# Codeshelf-0011_v01.net
KiCad netlist of a schematic drawn in EAGLE
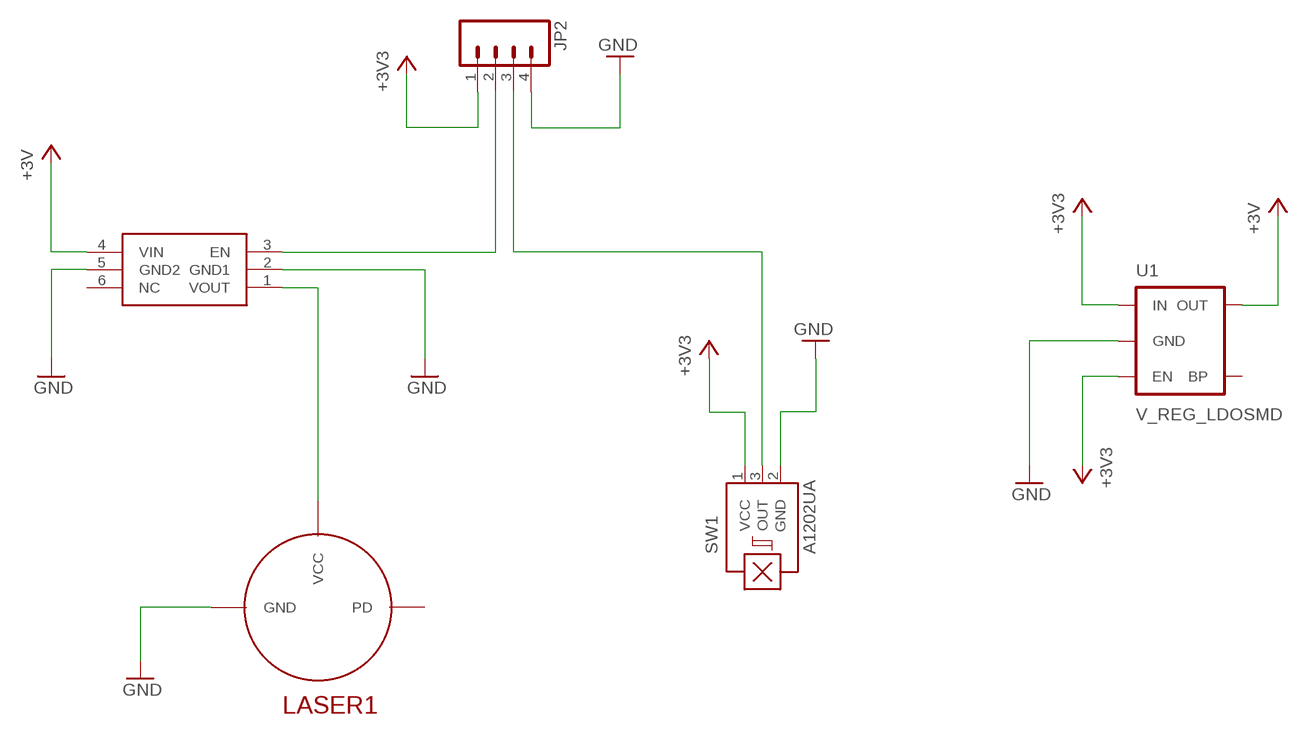
[diagram p0: schematic, sheet 1]

(export (version "E")
  (design (tool "Eeschema 10.0.6"))
  (components
    (comp (ref "JP2")
      (value "M04PTH")
      (footprint "eagle-import:1X04")
      (libsource (lib "eagle-import") (part "M04PTH"))
    )
    (comp (ref "LASER1")
      (value "LMAPCD-650-06")
      (footprint "eagle-import:LMAPCD-650-06")
      (libsource (lib "eagle-import") (part "LMAPCD-650-06"))
    )
    (comp (ref "SW1")
      (value "A1202UA")
      (footprint "eagle-import:SIP3-UA")
      (libsource (lib "eagle-import") (part "A12?UA02"))
    )
    (comp (ref "U1")
      (value "V_REG_LDOSMD")
      (footprint "eagle-import:SOT23-5")
      (libsource (lib "eagle-import") (part "V_REG_LDOSMD"))
    )
    (comp (ref "U2")
      (value "MIC94061C6")
      (footprint "eagle-import:SC70-6L")
      (libsource (lib "eagle-import") (part "MIC94061C6"))
    )
  )
  (nets
    (net (code "1") (name "+3V") (class "Default")
      (node (ref "U1") (pin "5") (pinfunction "OUT_5") (pintype "passive"))
      (node (ref "U2") (pin "4") (pinfunction "VIN_4") (pintype "bidirectional"))
    )
    (net (code "2") (name "+3V3") (class "Default")
      (node (ref "JP2") (pin "1") (pinfunction "1_1") (pintype "passive"))
      (node (ref "SW1") (pin "1") (pinfunction "VCC_1") (pintype "power_in"))
      (node (ref "U1") (pin "1") (pinfunction "IN_1") (pintype "input"))
      (node (ref "U1") (pin "3") (pinfunction "EN_3") (pintype "input"))
    )
    (net (code "3") (name "GND") (class "Default")
      (node (ref "JP2") (pin "4") (pinfunction "4_4") (pintype "passive"))
      (node (ref "LASER1") (pin "1") (pinfunction "GND_1") (pintype "power_in"))
      (node (ref "SW1") (pin "2") (pinfunction "GND_2") (pintype "power_in"))
      (node (ref "U1") (pin "2") (pinfunction "GND_2") (pintype "input"))
      (node (ref "U2") (pin "2") (pinfunction "GND1_2") (pintype "bidirectional"))
      (node (ref "U2") (pin "5") (pinfunction "GND2_5") (pintype "bidirectional"))
    )
    (net (code "4") (name "Net-(LASER1-VCC)") (class "Default")
      (node (ref "LASER1") (pin "2") (pinfunction "VCC_2") (pintype "power_in"))
      (node (ref "U2") (pin "1") (pinfunction "VOUT_1") (pintype "bidirectional"))
    )
    (net (code "5") (name "Net-(SW1-OUT)") (class "Default")
      (node (ref "JP2") (pin "3") (pinfunction "3_3") (pintype "passive"))
      (node (ref "SW1") (pin "3") (pinfunction "OUT_3") (pintype "output"))
    )
    (net (code "6") (name "Net-(U2-EN)") (class "Default")
      (node (ref "JP2") (pin "2") (pinfunction "2_2") (pintype "passive"))
      (node (ref "U2") (pin "3") (pinfunction "EN_3") (pintype "bidirectional"))
    )
    (net (code "7") (name "unconnected-(LASER1-PD-Pad3)") (class "Default")
      (node (ref "LASER1") (pin "3") (pinfunction "PD_3") (pintype "no_connect"))
    )
    (net (code "8") (name "unconnected-(U1-BP-Pad4)") (class "Default")
      (node (ref "U1") (pin "4") (pinfunction "BP_4") (pintype "input"))
    )
    (net (code "9") (name "unconnected-(U2-NC-Pad6)") (class "Default")
      (node (ref "U2") (pin "6") (pinfunction "NC_6") (pintype "bidirectional"))
    )
  )
)
